# uuni.net
KiCad netlist of a schematic drawn in EAGLE
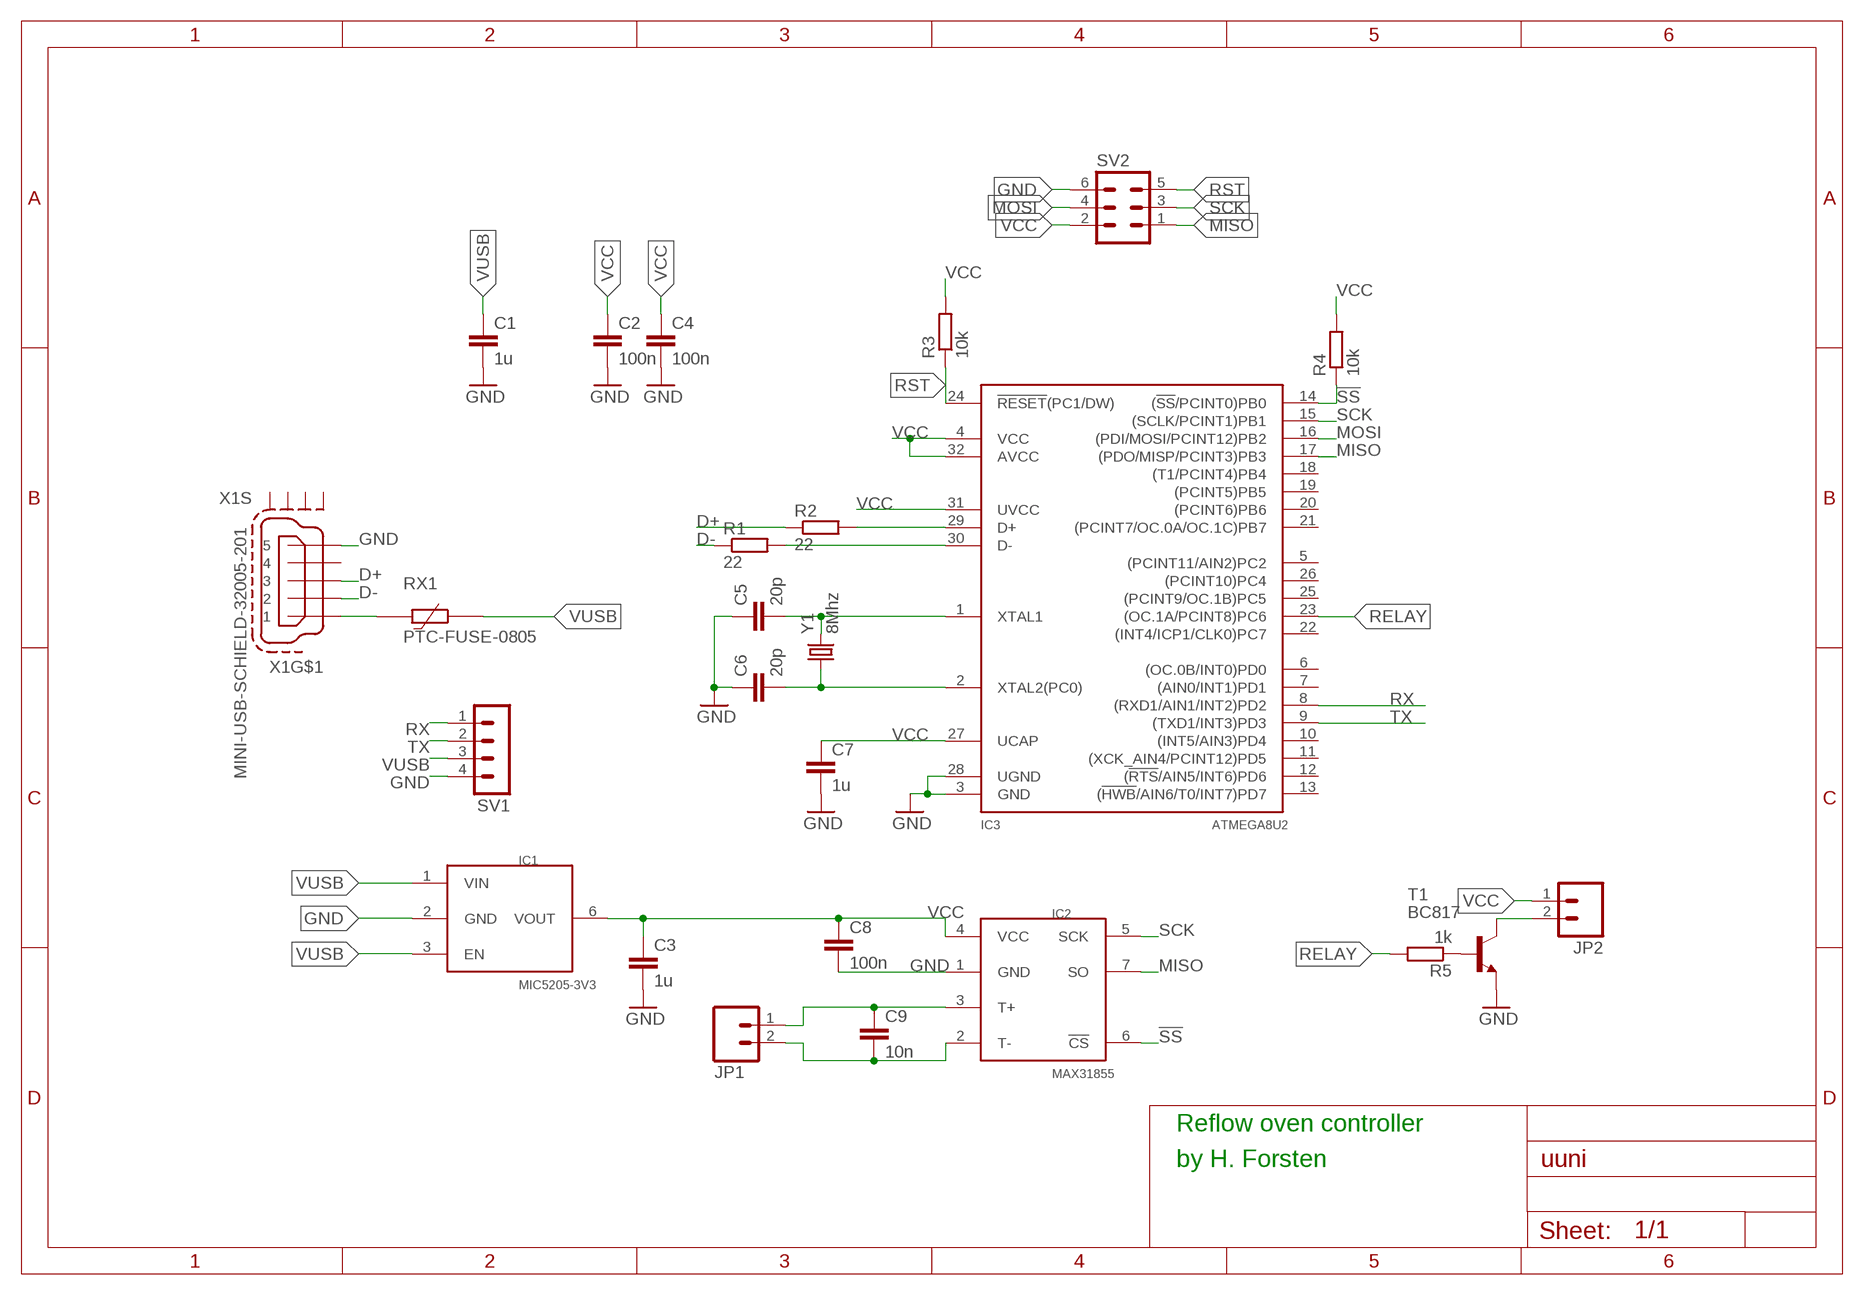
[diagram p0: schematic, sheet 1]

(export (version "E")
  (design (tool "Eeschema 10.0.6"))
  (components
    (comp (ref "C1")
      (value "1u")
      (footprint "eagle-import:C0603")
      (libsource (lib "eagle-import") (part "C-EUC0603"))
    )
    (comp (ref "C2")
      (value "100n")
      (footprint "eagle-import:C0402")
      (libsource (lib "eagle-import") (part "C-EUC0402"))
    )
    (comp (ref "C3")
      (value "1u")
      (footprint "eagle-import:C0603")
      (libsource (lib "eagle-import") (part "C-EUC0603"))
    )
    (comp (ref "C4")
      (value "100n")
      (footprint "eagle-import:C0402")
      (libsource (lib "eagle-import") (part "C-EUC0402"))
    )
    (comp (ref "C5")
      (value "20p")
      (footprint "eagle-import:C0603")
      (libsource (lib "eagle-import") (part "C-EUC0603"))
    )
    (comp (ref "C6")
      (value "20p")
      (footprint "eagle-import:C0603")
      (libsource (lib "eagle-import") (part "C-EUC0603"))
    )
    (comp (ref "C7")
      (value "1u")
      (footprint "eagle-import:C0603")
      (libsource (lib "eagle-import") (part "C-EUC0603"))
    )
    (comp (ref "C8")
      (value "100n")
      (footprint "eagle-import:C0402")
      (libsource (lib "eagle-import") (part "C-EUC0402"))
    )
    (comp (ref "C9")
      (value "10n")
      (footprint "eagle-import:C0603")
      (libsource (lib "eagle-import") (part "C-EUC0603"))
    )
    (comp (ref "IC1")
      (value "MIC5205-3V3")
      (footprint "eagle-import:SC-74")
      (libsource (lib "eagle-import") (part "FT531JA"))
    )
    (comp (ref "IC2")
      (value "MAX31855")
      (footprint "eagle-import:SO8")
      (libsource (lib "eagle-import") (part "MAX31855"))
    )
    (comp (ref "IC3")
      (value "ATMEGA8U2")
      (footprint "eagle-import:TQFP32-08")
      (libsource (lib "eagle-import") (part "ATMEGA8U2"))
    )
    (comp (ref "JP1")
      (value "M025MM")
      (footprint "eagle-import:SCREWTERMINAL-5MM-2")
      (libsource (lib "eagle-import") (part "M025MM"))
    )
    (comp (ref "JP2")
      (value "M02LOCK")
      (footprint "eagle-import:1X02_LOCK")
      (libsource (lib "eagle-import") (part "M02LOCK"))
    )
    (comp (ref "R1")
      (value "22")
      (footprint "eagle-import:R0603")
      (libsource (lib "eagle-import") (part "R-EU_R0603"))
    )
    (comp (ref "R2")
      (value "22")
      (footprint "eagle-import:R0603")
      (libsource (lib "eagle-import") (part "R-EU_R0603"))
    )
    (comp (ref "R3")
      (value "10k")
      (footprint "eagle-import:R0603")
      (libsource (lib "eagle-import") (part "R-EU_R0603"))
    )
    (comp (ref "R4")
      (value "10k")
      (footprint "eagle-import:R0603")
      (libsource (lib "eagle-import") (part "R-EU_R0603"))
    )
    (comp (ref "R5")
      (value "1k")
      (footprint "eagle-import:R0603")
      (libsource (lib "eagle-import") (part "R-EU_R0603"))
    )
    (comp (ref "RX1")
      (value "PTC-FUSE-0805")
      (footprint "eagle-import:R0805")
      (libsource (lib "eagle-import") (part "PTC-FUSE-0805"))
    )
    (comp (ref "SV1")
      (value "MA04-1")
      (footprint "eagle-import:MA04-1")
      (libsource (lib "eagle-import") (part "MA04-1"))
    )
    (comp (ref "SV2")
      (value "MA03-2")
      (footprint "eagle-import:MA03-2")
      (libsource (lib "eagle-import") (part "MA03-2"))
    )
    (comp (ref "T1")
      (value "BC817")
      (footprint "eagle-import:SOT23-BEC")
      (libsource (lib "eagle-import") (part "-NPN-SOT23-BECBC817-40"))
    )
    (comp (ref "X1")
      (value "MINI-USB-SCHIELD-32005-201")
      (footprint "eagle-import:32005-201")
      (libsource (lib "eagle-import") (part "MINI-USB-SCHIELD-32005-201"))
    )
    (comp (ref "Y1")
      (value "8Mhz")
      (footprint "eagle-import:HC49UP")
      (libsource (lib "eagle-import") (part "CRYSTALSMD"))
    )
  )
  (nets
    (net (code "1") (name "/D+") (class "Default")
      (node (ref "R2") (pin "1") (pinfunction "1_1") (pintype "passive"))
      (node (ref "X1") (pin "3") (pinfunction "3_3") (pintype "passive"))
    )
    (net (code "2") (name "/D-") (class "Default")
      (node (ref "R1") (pin "1") (pinfunction "1_1") (pintype "passive"))
      (node (ref "X1") (pin "2") (pinfunction "2_2") (pintype "passive"))
    )
    (net (code "3") (name "/RX") (class "Default")
      (node (ref "IC3") (pin "8") (pinfunction "(RXD1/AIN1/INT2)PD2_8") (pintype "bidirectional"))
      (node (ref "SV1") (pin "1") (pinfunction "1_1") (pintype "passive"))
    )
    (net (code "4") (name "/TX") (class "Default")
      (node (ref "IC3") (pin "9") (pinfunction "(TXD1/INT3)PD3_9") (pintype "bidirectional"))
      (node (ref "SV1") (pin "2") (pinfunction "2_2") (pintype "passive"))
    )
    (net (code "5") (name "/~{SS}") (class "Default")
      (node (ref "IC2") (pin "6") (pinfunction "~{CS}_6") (pintype "bidirectional"))
      (node (ref "IC3") (pin "14") (pinfunction "(~{SS}/PCINT0)PB0_14") (pintype "bidirectional"))
      (node (ref "R4") (pin "1") (pinfunction "1_1") (pintype "passive"))
    )
    (net (code "6") (name "GND") (class "Default")
      (node (ref "C1") (pin "2") (pinfunction "2_2") (pintype "passive"))
      (node (ref "C2") (pin "2") (pinfunction "2_2") (pintype "passive"))
      (node (ref "C3") (pin "2") (pinfunction "2_2") (pintype "passive"))
      (node (ref "C4") (pin "2") (pinfunction "2_2") (pintype "passive"))
      (node (ref "C5") (pin "1") (pinfunction "1_1") (pintype "passive"))
      (node (ref "C6") (pin "1") (pinfunction "1_1") (pintype "passive"))
      (node (ref "C7") (pin "2") (pinfunction "2_2") (pintype "passive"))
      (node (ref "C8") (pin "2") (pinfunction "2_2") (pintype "passive"))
      (node (ref "IC1") (pin "2") (pinfunction "GND_2") (pintype "bidirectional"))
      (node (ref "IC2") (pin "1") (pinfunction "GND_1") (pintype "bidirectional"))
      (node (ref "IC3") (pin "28") (pinfunction "UGND_28") (pintype "bidirectional"))
      (node (ref "IC3") (pin "3") (pinfunction "GND_3") (pintype "bidirectional"))
      (node (ref "SV1") (pin "4") (pinfunction "4_4") (pintype "passive"))
      (node (ref "SV2") (pin "6") (pinfunction "6_6") (pintype "passive"))
      (node (ref "T1") (pin "E") (pinfunction "E_E") (pintype "passive"))
      (node (ref "X1") (pin "5") (pinfunction "5_5") (pintype "passive"))
    )
    (net (code "7") (name "MISO") (class "Default")
      (node (ref "IC2") (pin "7") (pinfunction "SO_7") (pintype "bidirectional"))
      (node (ref "IC3") (pin "17") (pinfunction "(PDO/MISP/PCINT3)PB3_17") (pintype "bidirectional"))
      (node (ref "SV2") (pin "1") (pinfunction "1_1") (pintype "passive"))
    )
    (net (code "8") (name "MOSI") (class "Default")
      (node (ref "IC3") (pin "16") (pinfunction "(PDI/MOSI/PCINT12)PB2_16") (pintype "bidirectional"))
      (node (ref "SV2") (pin "4") (pinfunction "4_4") (pintype "passive"))
    )
    (net (code "9") (name "Net-(IC2-T+)") (class "Default")
      (node (ref "C9") (pin "1") (pinfunction "1_1") (pintype "passive"))
      (node (ref "IC2") (pin "3") (pinfunction "T+_3") (pintype "bidirectional"))
      (node (ref "JP1") (pin "1") (pinfunction "1_1") (pintype "passive"))
    )
    (net (code "10") (name "Net-(IC2-T-)") (class "Default")
      (node (ref "C9") (pin "2") (pinfunction "2_2") (pintype "passive"))
      (node (ref "IC2") (pin "2") (pinfunction "T-_2") (pintype "bidirectional"))
      (node (ref "JP1") (pin "2") (pinfunction "2_2") (pintype "passive"))
    )
    (net (code "11") (name "Net-(IC3-D+)") (class "Default")
      (node (ref "IC3") (pin "29") (pinfunction "D+_29") (pintype "bidirectional"))
      (node (ref "R2") (pin "2") (pinfunction "2_2") (pintype "passive"))
    )
    (net (code "12") (name "Net-(IC3-D-)") (class "Default")
      (node (ref "IC3") (pin "30") (pinfunction "D-_30") (pintype "bidirectional"))
      (node (ref "R1") (pin "2") (pinfunction "2_2") (pintype "passive"))
    )
    (net (code "13") (name "Net-(IC3-XTAL1)") (class "Default")
      (node (ref "C5") (pin "2") (pinfunction "2_2") (pintype "passive"))
      (node (ref "IC3") (pin "1") (pinfunction "XTAL1_1") (pintype "bidirectional"))
      (node (ref "Y1") (pin "2") (pinfunction "2_2") (pintype "passive"))
    )
    (net (code "14") (name "Net-(IC3-XTAL2(PC0))") (class "Default")
      (node (ref "C6") (pin "2") (pinfunction "2_2") (pintype "passive"))
      (node (ref "IC3") (pin "2") (pinfunction "XTAL2(PC0)_2") (pintype "bidirectional"))
      (node (ref "Y1") (pin "1") (pinfunction "1_1") (pintype "passive"))
    )
    (net (code "15") (name "Net-(JP2-Pad2)") (class "Default")
      (node (ref "JP2") (pin "2") (pinfunction "2_2") (pintype "passive"))
      (node (ref "T1") (pin "C") (pinfunction "C_C") (pintype "passive"))
    )
    (net (code "16") (name "Net-(R5-Pad1)") (class "Default")
      (node (ref "R5") (pin "1") (pinfunction "1_1") (pintype "passive"))
      (node (ref "T1") (pin "B") (pinfunction "B_B") (pintype "passive"))
    )
    (net (code "17") (name "Net-(RX1-P$1)") (class "Default")
      (node (ref "RX1") (pin "1") (pinfunction "P$1_1") (pintype "bidirectional"))
      (node (ref "X1") (pin "1") (pinfunction "1_1") (pintype "passive"))
    )
    (net (code "18") (name "RELAY") (class "Default")
      (node (ref "IC3") (pin "23") (pinfunction "(OC.1A/PCINT8)PC6_23") (pintype "bidirectional"))
      (node (ref "R5") (pin "2") (pinfunction "2_2") (pintype "passive"))
    )
    (net (code "19") (name "RST") (class "Default")
      (node (ref "IC3") (pin "24") (pinfunction "~{RESET}(PC1/DW)_24") (pintype "bidirectional"))
      (node (ref "R3") (pin "1") (pinfunction "1_1") (pintype "passive"))
      (node (ref "SV2") (pin "5") (pinfunction "5_5") (pintype "passive"))
    )
    (net (code "20") (name "SCK") (class "Default")
      (node (ref "IC2") (pin "5") (pinfunction "SCK_5") (pintype "bidirectional"))
      (node (ref "IC3") (pin "15") (pinfunction "(SCLK/PCINT1)PB1_15") (pintype "bidirectional"))
      (node (ref "SV2") (pin "3") (pinfunction "3_3") (pintype "passive"))
    )
    (net (code "21") (name "VCC") (class "Default")
      (node (ref "C2") (pin "1") (pinfunction "1_1") (pintype "passive"))
      (node (ref "C3") (pin "1") (pinfunction "1_1") (pintype "passive"))
      (node (ref "C4") (pin "1") (pinfunction "1_1") (pintype "passive"))
      (node (ref "C7") (pin "1") (pinfunction "1_1") (pintype "passive"))
      (node (ref "C8") (pin "1") (pinfunction "1_1") (pintype "passive"))
      (node (ref "IC1") (pin "6") (pinfunction "VOUT_6") (pintype "bidirectional"))
      (node (ref "IC2") (pin "4") (pinfunction "VCC_4") (pintype "bidirectional"))
      (node (ref "IC3") (pin "27") (pinfunction "UCAP_27") (pintype "bidirectional"))
      (node (ref "IC3") (pin "31") (pinfunction "UVCC_31") (pintype "bidirectional"))
      (node (ref "IC3") (pin "32") (pinfunction "AVCC_32") (pintype "bidirectional"))
      (node (ref "IC3") (pin "4") (pinfunction "VCC_4") (pintype "bidirectional"))
      (node (ref "JP2") (pin "1") (pinfunction "1_1") (pintype "passive"))
      (node (ref "R3") (pin "2") (pinfunction "2_2") (pintype "passive"))
      (node (ref "R4") (pin "2") (pinfunction "2_2") (pintype "passive"))
      (node (ref "SV2") (pin "2") (pinfunction "2_2") (pintype "passive"))
    )
    (net (code "22") (name "VUSB") (class "Default")
      (node (ref "C1") (pin "1") (pinfunction "1_1") (pintype "passive"))
      (node (ref "IC1") (pin "1") (pinfunction "VIN_1") (pintype "bidirectional"))
      (node (ref "IC1") (pin "3") (pinfunction "EN_3") (pintype "bidirectional"))
      (node (ref "RX1") (pin "2") (pinfunction "P$2_2") (pintype "bidirectional"))
      (node (ref "SV1") (pin "3") (pinfunction "3_3") (pintype "passive"))
    )
    (net (code "23") (name "unconnected-(IC3-(AIN0{slash}INT1)PD1-Pad7)") (class "Default")
      (node (ref "IC3") (pin "7") (pinfunction "(AIN0/INT1)PD1_7") (pintype "bidirectional"))
    )
    (net (code "24") (name "unconnected-(IC3-(INT4{slash}ICP1{slash}CLK0)PC7-Pad22)") (class "Default")
      (node (ref "IC3") (pin "22") (pinfunction "(INT4/ICP1/CLK0)PC7_22") (pintype "bidirectional"))
    )
    (net (code "25") (name "unconnected-(IC3-(INT5{slash}AIN3)PD4-Pad10)") (class "Default")
      (node (ref "IC3") (pin "10") (pinfunction "(INT5/AIN3)PD4_10") (pintype "bidirectional"))
    )
    (net (code "26") (name "unconnected-(IC3-(OC.0B{slash}INT0)PD0-Pad6)") (class "Default")
      (node (ref "IC3") (pin "6") (pinfunction "(OC.0B/INT0)PD0_6") (pintype "bidirectional"))
    )
    (net (code "27") (name "unconnected-(IC3-(PCINT5)PB5-Pad19)") (class "Default")
      (node (ref "IC3") (pin "19") (pinfunction "(PCINT5)PB5_19") (pintype "bidirectional"))
    )
    (net (code "28") (name "unconnected-(IC3-(PCINT6)PB6-Pad20)") (class "Default")
      (node (ref "IC3") (pin "20") (pinfunction "(PCINT6)PB6_20") (pintype "bidirectional"))
    )
    (net (code "29") (name "unconnected-(IC3-(PCINT7{slash}OC.0A{slash}OC.1C)PB7-Pad21)") (class "Default")
      (node (ref "IC3") (pin "21") (pinfunction "(PCINT7/OC.0A/OC.1C)PB7_21") (pintype "bidirectional"))
    )
    (net (code "30") (name "unconnected-(IC3-(PCINT9{slash}OC.1B)PC5-Pad25)") (class "Default")
      (node (ref "IC3") (pin "25") (pinfunction "(PCINT9/OC.1B)PC5_25") (pintype "bidirectional"))
    )
    (net (code "31") (name "unconnected-(IC3-(PCINT10)PC4-Pad26)") (class "Default")
      (node (ref "IC3") (pin "26") (pinfunction "(PCINT10)PC4_26") (pintype "bidirectional"))
    )
    (net (code "32") (name "unconnected-(IC3-(PCINT11{slash}AIN2)PC2-Pad5)") (class "Default")
      (node (ref "IC3") (pin "5") (pinfunction "(PCINT11/AIN2)PC2_5") (pintype "bidirectional"))
    )
    (net (code "33") (name "unconnected-(IC3-(T1{slash}PCINT4)PB4-Pad18)") (class "Default")
      (node (ref "IC3") (pin "18") (pinfunction "(T1/PCINT4)PB4_18") (pintype "bidirectional"))
    )
    (net (code "34") (name "unconnected-(IC3-(XCK_AIN4{slash}PCINT12)PD5-Pad11)") (class "Default")
      (node (ref "IC3") (pin "11") (pinfunction "(XCK_AIN4/PCINT12)PD5_11") (pintype "bidirectional"))
    )
    (net (code "35") (name "unconnected-(IC3-(~{HWB}{slash}AIN6{slash}T0{slash}INT7)PD7-Pad13)") (class "Default")
      (node (ref "IC3") (pin "13") (pinfunction "(~{HWB}/AIN6/T0/INT7)PD7_13") (pintype "bidirectional"))
    )
    (net (code "36") (name "unconnected-(IC3-(~{RTS}{slash}AIN5{slash}INT6)PD6-Pad12)") (class "Default")
      (node (ref "IC3") (pin "12") (pinfunction "(~{RTS}/AIN5/INT6)PD6_12") (pintype "bidirectional"))
    )
    (net (code "37") (name "unconnected-(X1-Pad4)") (class "Default")
      (node (ref "X1") (pin "4") (pinfunction "4_4") (pintype "passive"))
    )
    (net (code "38") (name "unconnected-(X1B-S1-PadM1)") (class "Default")
      (node (ref "X1") (pin "M1") (pinfunction "S1_M1") (pintype "passive"))
    )
    (net (code "39") (name "unconnected-(X1B-S2-PadM2)") (class "Default")
      (node (ref "X1") (pin "M2") (pinfunction "S2_M2") (pintype "passive"))
    )
    (net (code "40") (name "unconnected-(X1B-S3-PadM3)") (class "Default")
      (node (ref "X1") (pin "M3") (pinfunction "S3_M3") (pintype "passive"))
    )
    (net (code "41") (name "unconnected-(X1B-S4-PadM4)") (class "Default")
      (node (ref "X1") (pin "M4") (pinfunction "S4_M4") (pintype "passive"))
    )
  )
)
